# fre_oa.net
KiCad netlist of a schematic drawn in Altium Designer
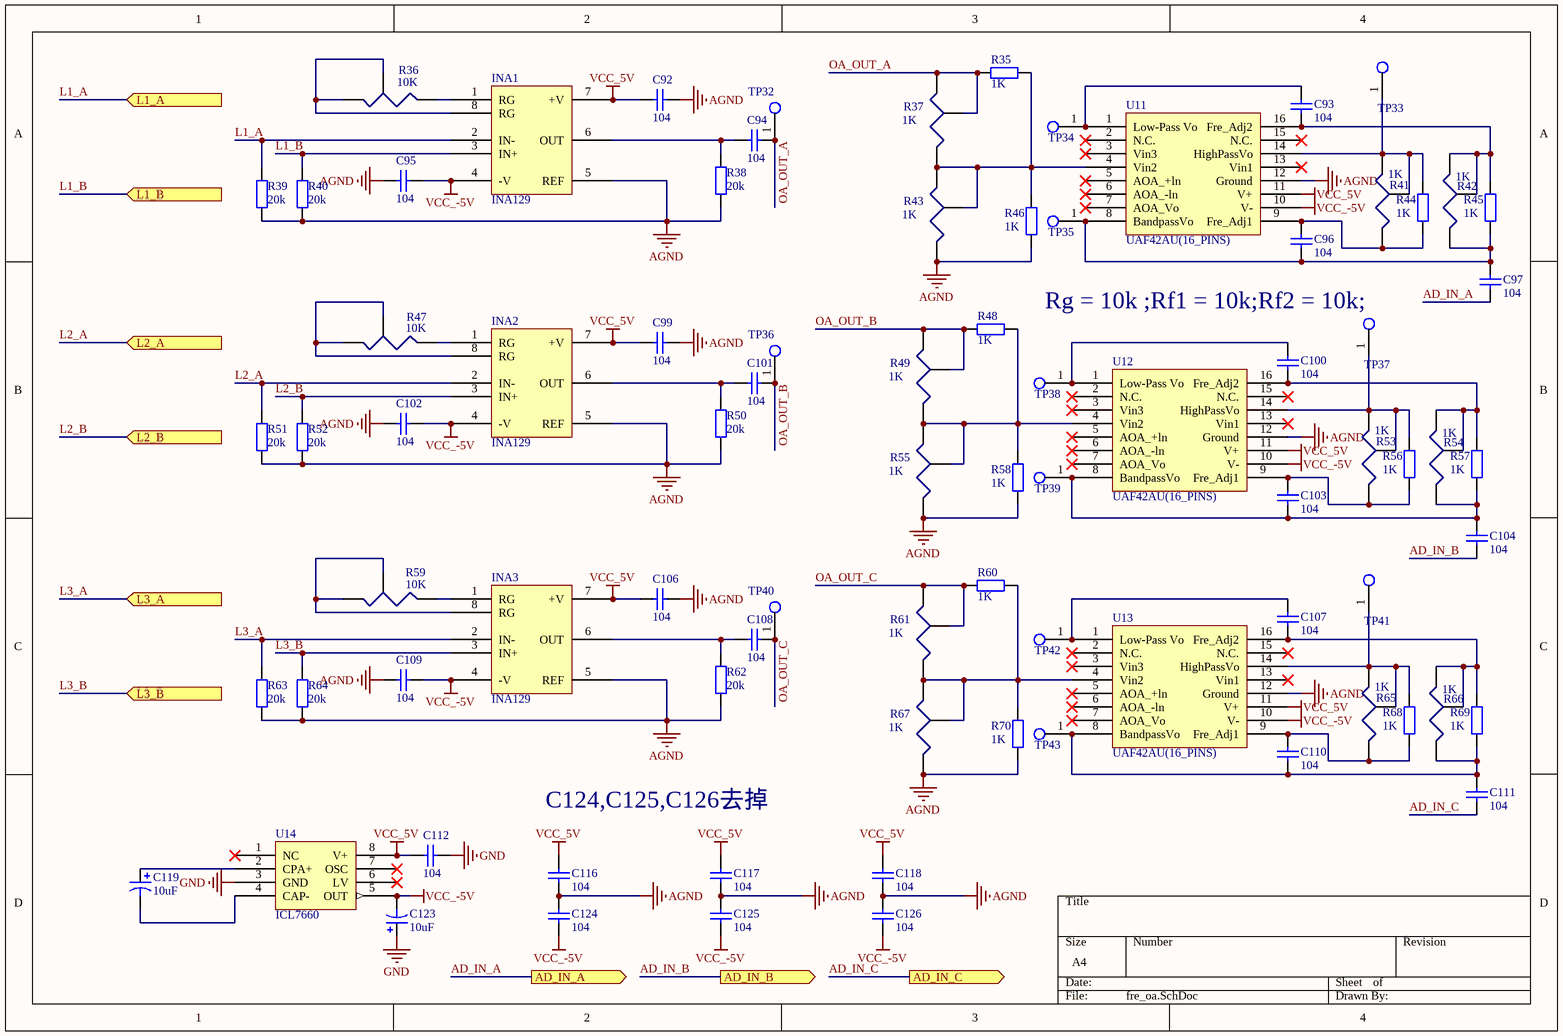
[diagram p0: fre_oa.SchDoc]

(export (version "E")
  (design (tool "Eeschema 10.0.6"))
  (components
    (comp (ref "C92")
      (value "104")
      (footprint "0603")
      (fields (field (name "Comment") "Cap"))
      (libsource (lib "自动化研究所集成库20170318") (part "Cap"))
    )
    (comp (ref "C93")
      (value "104")
      (footprint "0603")
      (fields (field (name "Comment") "Cap"))
      (libsource (lib "自动化研究所集成库20170318") (part "Cap"))
    )
    (comp (ref "C94")
      (value "104")
      (footprint "0603")
      (fields (field (name "Comment") "Cap"))
      (libsource (lib "自动化研究所集成库20170318") (part "Cap"))
    )
    (comp (ref "C95")
      (value "104")
      (footprint "0603")
      (fields (field (name "Comment") "Cap"))
      (libsource (lib "自动化研究所集成库20170318") (part "Cap"))
    )
    (comp (ref "C96")
      (value "104")
      (footprint "0603")
      (fields (field (name "Comment") "Cap"))
      (libsource (lib "自动化研究所集成库20170318") (part "Cap"))
    )
    (comp (ref "C97")
      (value "104")
      (footprint "0603")
      (fields (field (name "Comment") "Cap"))
      (libsource (lib "自动化研究所集成库20170318") (part "Cap"))
    )
    (comp (ref "C99")
      (value "104")
      (footprint "0603")
      (fields (field (name "Comment") "Cap"))
      (libsource (lib "自动化研究所集成库20170318") (part "Cap"))
    )
    (comp (ref "C100")
      (value "104")
      (footprint "0603")
      (fields (field (name "Comment") "Cap"))
      (libsource (lib "自动化研究所集成库20170318") (part "Cap"))
    )
    (comp (ref "C101")
      (value "104")
      (footprint "0603")
      (fields (field (name "Comment") "Cap"))
      (libsource (lib "自动化研究所集成库20170318") (part "Cap"))
    )
    (comp (ref "C102")
      (value "104")
      (footprint "0603")
      (fields (field (name "Comment") "Cap"))
      (libsource (lib "自动化研究所集成库20170318") (part "Cap"))
    )
    (comp (ref "C103")
      (value "104")
      (footprint "0603")
      (fields (field (name "Comment") "Cap"))
      (libsource (lib "自动化研究所集成库20170318") (part "Cap"))
    )
    (comp (ref "C104")
      (value "104")
      (footprint "0603")
      (fields (field (name "Comment") "Cap"))
      (libsource (lib "自动化研究所集成库20170318") (part "Cap"))
    )
    (comp (ref "C106")
      (value "104")
      (footprint "0603")
      (fields (field (name "Comment") "Cap"))
      (libsource (lib "自动化研究所集成库20170318") (part "Cap"))
    )
    (comp (ref "C107")
      (value "104")
      (footprint "0603")
      (fields (field (name "Comment") "Cap"))
      (libsource (lib "自动化研究所集成库20170318") (part "Cap"))
    )
    (comp (ref "C108")
      (value "104")
      (footprint "0603")
      (fields (field (name "Comment") "Cap"))
      (libsource (lib "自动化研究所集成库20170318") (part "Cap"))
    )
    (comp (ref "C109")
      (value "104")
      (footprint "0603")
      (fields (field (name "Comment") "Cap"))
      (libsource (lib "自动化研究所集成库20170318") (part "Cap"))
    )
    (comp (ref "C110")
      (value "104")
      (footprint "0603")
      (fields (field (name "Comment") "Cap"))
      (libsource (lib "自动化研究所集成库20170318") (part "Cap"))
    )
    (comp (ref "C111")
      (value "104")
      (footprint "0603")
      (fields (field (name "Comment") "Cap"))
      (libsource (lib "自动化研究所集成库20170318") (part "Cap"))
    )
    (comp (ref "C112")
      (value "104")
      (footprint "0603")
      (fields (field (name "Comment") "Cap"))
      (libsource (lib "自动化研究所集成库20170318") (part "Cap"))
    )
    (comp (ref "C116")
      (value "104")
      (footprint "0603")
      (fields (field (name "Comment") "Cap"))
      (libsource (lib "自动化研究所集成库20170318") (part "Cap"))
    )
    (comp (ref "C117")
      (value "104")
      (footprint "0603")
      (fields (field (name "Comment") "Cap"))
      (libsource (lib "自动化研究所集成库20170318") (part "Cap"))
    )
    (comp (ref "C118")
      (value "104")
      (footprint "0603")
      (fields (field (name "Comment") "Cap"))
      (libsource (lib "自动化研究所集成库20170318") (part "Cap"))
    )
    (comp (ref "C119")
      (value "10uF")
      (footprint "Cap 3528B")
      (fields (field (name "Comment") "Cap Poll"))
      (libsource (lib "自动化研究所集成库20170318") (part "Cap Poll"))
    )
    (comp (ref "C123")
      (value "10uF")
      (footprint "Cap 3528B")
      (fields (field (name "Comment") "Cap Poll"))
      (libsource (lib "自动化研究所集成库20170318") (part "Cap Poll"))
    )
    (comp (ref "C124")
      (value "104")
      (footprint "0603")
      (fields (field (name "Comment") "Cap"))
      (libsource (lib "自动化研究所集成库20170318") (part "Cap"))
    )
    (comp (ref "C125")
      (value "104")
      (footprint "0603")
      (fields (field (name "Comment") "Cap"))
      (libsource (lib "自动化研究所集成库20170318") (part "Cap"))
    )
    (comp (ref "C126")
      (value "104")
      (footprint "0603")
      (fields (field (name "Comment") "Cap"))
      (libsource (lib "自动化研究所集成库20170318") (part "Cap"))
    )
    (comp (ref "INA1") (value "INA129") (footprint "LM386") (libsource (lib "Sensor") (part "INA129")))
    (comp (ref "INA2") (value "INA129") (footprint "LM386") (libsource (lib "Sensor") (part "INA129")))
    (comp (ref "INA3") (value "INA129") (footprint "LM386") (libsource (lib "Sensor") (part "INA129")))
    (comp (ref "R35")
      (value "1K")
      (footprint "0603")
      (fields (field (name "Comment") "Res"))
      (libsource (lib "") (part "Res_1"))
    )
    (comp (ref "R36")
      (value "10K")
      (footprint "电位器WH06-2C")
      (fields (field (name "Comment") "电位器"))
      (libsource (lib "自动化研究所集成库20170318") (part "电位器"))
    )
    (comp (ref "R37")
      (value "1K")
      (footprint "电位器WH06-2C")
      (fields (field (name "Comment") "电位器"))
      (libsource (lib "自动化研究所集成库20170318") (part "电位器"))
    )
    (comp (ref "R38")
      (value "20k")
      (footprint "0603")
      (fields (field (name "Comment") "Res"))
      (libsource (lib "自动化研究所集成库20170318") (part "Res"))
    )
    (comp (ref "R39")
      (value "20k")
      (footprint "0603")
      (fields (field (name "Comment") "Res"))
      (libsource (lib "自动化研究所集成库20170318") (part "Res"))
    )
    (comp (ref "R40")
      (value "20k")
      (footprint "0603")
      (fields (field (name "Comment") "Res"))
      (libsource (lib "自动化研究所集成库20170318") (part "Res"))
    )
    (comp (ref "R41")
      (value "1K")
      (footprint "电位器WH06-2C")
      (fields (field (name "Comment") "电位器"))
      (libsource (lib "自动化研究所集成库20170318") (part "电位器"))
    )
    (comp (ref "R42")
      (value "1K")
      (footprint "电位器WH06-2C")
      (fields (field (name "Comment") "电位器"))
      (libsource (lib "自动化研究所集成库20170318") (part "电位器"))
    )
    (comp (ref "R43")
      (value "1K")
      (footprint "电位器WH06-2C")
      (fields (field (name "Comment") "电位器"))
      (libsource (lib "自动化研究所集成库20170318") (part "电位器"))
    )
    (comp (ref "R44")
      (value "1K")
      (footprint "0603")
      (fields (field (name "Comment") "Res"))
      (libsource (lib "自动化研究所集成库20170318") (part "Res"))
    )
    (comp (ref "R45")
      (value "1K")
      (footprint "0603")
      (fields (field (name "Comment") "Res"))
      (libsource (lib "自动化研究所集成库20170318") (part "Res"))
    )
    (comp (ref "R46")
      (value "1K")
      (footprint "0603")
      (fields (field (name "Comment") "Res"))
      (libsource (lib "自动化研究所集成库20170318") (part "Res"))
    )
    (comp (ref "R47")
      (value "10K")
      (footprint "电位器WH06-2C")
      (fields (field (name "Comment") "电位器"))
      (libsource (lib "自动化研究所集成库20170318") (part "电位器"))
    )
    (comp (ref "R48")
      (value "1K")
      (footprint "0603")
      (fields (field (name "Comment") "Res"))
      (libsource (lib "") (part "Res_1"))
    )
    (comp (ref "R49")
      (value "1K")
      (footprint "电位器WH06-2C")
      (fields (field (name "Comment") "电位器"))
      (libsource (lib "自动化研究所集成库20170318") (part "电位器"))
    )
    (comp (ref "R50")
      (value "20k")
      (footprint "0603")
      (fields (field (name "Comment") "Res"))
      (libsource (lib "自动化研究所集成库20170318") (part "Res"))
    )
    (comp (ref "R51")
      (value "20k")
      (footprint "0603")
      (fields (field (name "Comment") "Res"))
      (libsource (lib "自动化研究所集成库20170318") (part "Res"))
    )
    (comp (ref "R52")
      (value "20k")
      (footprint "0603")
      (fields (field (name "Comment") "Res"))
      (libsource (lib "自动化研究所集成库20170318") (part "Res"))
    )
    (comp (ref "R53")
      (value "1K")
      (footprint "电位器WH06-2C")
      (fields (field (name "Comment") "电位器"))
      (libsource (lib "自动化研究所集成库20170318") (part "电位器"))
    )
    (comp (ref "R54")
      (value "1K")
      (footprint "电位器WH06-2C")
      (fields (field (name "Comment") "电位器"))
      (libsource (lib "自动化研究所集成库20170318") (part "电位器"))
    )
    (comp (ref "R55")
      (value "1K")
      (footprint "电位器WH06-2C")
      (fields (field (name "Comment") "电位器"))
      (libsource (lib "自动化研究所集成库20170318") (part "电位器"))
    )
    (comp (ref "R56")
      (value "1K")
      (footprint "0603")
      (fields (field (name "Comment") "Res"))
      (libsource (lib "自动化研究所集成库20170318") (part "Res"))
    )
    (comp (ref "R57")
      (value "1K")
      (footprint "0603")
      (fields (field (name "Comment") "Res"))
      (libsource (lib "自动化研究所集成库20170318") (part "Res"))
    )
    (comp (ref "R58")
      (value "1K")
      (footprint "0603")
      (fields (field (name "Comment") "Res"))
      (libsource (lib "自动化研究所集成库20170318") (part "Res"))
    )
    (comp (ref "R59")
      (value "10K")
      (footprint "电位器WH06-2C")
      (fields (field (name "Comment") "电位器"))
      (libsource (lib "自动化研究所集成库20170318") (part "电位器"))
    )
    (comp (ref "R60")
      (value "1K")
      (footprint "0603")
      (fields (field (name "Comment") "Res"))
      (libsource (lib "") (part "Res_1"))
    )
    (comp (ref "R61")
      (value "1K")
      (footprint "电位器WH06-2C")
      (fields (field (name "Comment") "电位器"))
      (libsource (lib "自动化研究所集成库20170318") (part "电位器"))
    )
    (comp (ref "R62")
      (value "20k")
      (footprint "0603")
      (fields (field (name "Comment") "Res"))
      (libsource (lib "自动化研究所集成库20170318") (part "Res"))
    )
    (comp (ref "R63")
      (value "20k")
      (footprint "0603")
      (fields (field (name "Comment") "Res"))
      (libsource (lib "自动化研究所集成库20170318") (part "Res"))
    )
    (comp (ref "R64")
      (value "20k")
      (footprint "0603")
      (fields (field (name "Comment") "Res"))
      (libsource (lib "自动化研究所集成库20170318") (part "Res"))
    )
    (comp (ref "R65")
      (value "1K")
      (footprint "电位器WH06-2C")
      (fields (field (name "Comment") "电位器"))
      (libsource (lib "自动化研究所集成库20170318") (part "电位器"))
    )
    (comp (ref "R66")
      (value "1K")
      (footprint "电位器WH06-2C")
      (fields (field (name "Comment") "电位器"))
      (libsource (lib "自动化研究所集成库20170318") (part "电位器"))
    )
    (comp (ref "R67")
      (value "1K")
      (footprint "电位器WH06-2C")
      (fields (field (name "Comment") "电位器"))
      (libsource (lib "自动化研究所集成库20170318") (part "电位器"))
    )
    (comp (ref "R68")
      (value "1K")
      (footprint "0603")
      (fields (field (name "Comment") "Res"))
      (libsource (lib "自动化研究所集成库20170318") (part "Res"))
    )
    (comp (ref "R69")
      (value "1K")
      (footprint "0603")
      (fields (field (name "Comment") "Res"))
      (libsource (lib "自动化研究所集成库20170318") (part "Res"))
    )
    (comp (ref "R70")
      (value "1K")
      (footprint "0603")
      (fields (field (name "Comment") "Res"))
      (libsource (lib "自动化研究所集成库20170318") (part "Res"))
    )
    (comp (ref "TP32") (value "testPoint") (footprint "TP_H") (libsource (lib "Spartan") (part "TP")))
    (comp (ref "TP33") (value "testPoint") (footprint "TP_H") (libsource (lib "Spartan") (part "TP")))
    (comp (ref "TP34") (value "testPoint") (footprint "TP_H") (libsource (lib "Spartan") (part "TP")))
    (comp (ref "TP35") (value "testPoint") (footprint "TP_H") (libsource (lib "Spartan") (part "TP")))
    (comp (ref "TP36") (value "testPoint") (footprint "TP_H") (libsource (lib "Spartan") (part "TP")))
    (comp (ref "TP37") (value "testPoint") (footprint "TP_H") (libsource (lib "Spartan") (part "TP")))
    (comp (ref "TP38") (value "testPoint") (footprint "TP_H") (libsource (lib "Spartan") (part "TP")))
    (comp (ref "TP39") (value "testPoint") (footprint "TP_H") (libsource (lib "Spartan") (part "TP")))
    (comp (ref "TP40") (value "testPoint") (footprint "TP_H") (libsource (lib "Spartan") (part "TP")))
    (comp (ref "TP41") (value "testPoint") (footprint "TP_H") (libsource (lib "Spartan") (part "TP")))
    (comp (ref "TP42") (value "testPoint") (footprint "TP_H") (libsource (lib "Spartan") (part "TP")))
    (comp (ref "TP43") (value "testPoint") (footprint "TP_H") (libsource (lib "Spartan") (part "TP")))
    (comp (ref "U11")
      (value "UAF42AU(16_PINS)")
      (footprint "SOIC127P1030X265-16N")
      (libsource (lib "Dugu") (part "UAF42AU(16_PINS)"))
    )
    (comp (ref "U12")
      (value "UAF42AU(16_PINS)")
      (footprint "SOIC127P1030X265-16N")
      (libsource (lib "Dugu") (part "UAF42AU(16_PINS)"))
    )
    (comp (ref "U13")
      (value "UAF42AU(16_PINS)")
      (footprint "SOIC127P1030X265-16N")
      (libsource (lib "Dugu") (part "UAF42AU(16_PINS)"))
    )
    (comp (ref "U14")
      (value "ICL7660")
      (footprint "ICL7660 sop-8")
      (libsource (lib "自动化研究所集成库20170318") (part "ICL7660"))
    )
  )
  (nets
    (net (code "1") (name "/AD_IN_A") (class "Default")
      (node (ref "C97") (pin "2") (pinfunction "2_2") (pintype "passive"))
    )
    (net (code "2") (name "/AD_IN_B") (class "Default")
      (node (ref "C104") (pin "2") (pinfunction "2_2") (pintype "passive"))
    )
    (net (code "3") (name "/AD_IN_C") (class "Default")
      (node (ref "C111") (pin "2") (pinfunction "2_2") (pintype "passive"))
    )
    (net (code "4") (name "/L1_A") (class "Default")
      (node (ref "INA1") (pin "2") (pinfunction "IN-_2") (pintype "passive"))
      (node (ref "R39") (pin "2") (pinfunction "2_2") (pintype "passive"))
    )
    (net (code "5") (name "/L1_B") (class "Default")
      (node (ref "INA1") (pin "3") (pinfunction "IN+_3") (pintype "passive"))
      (node (ref "R40") (pin "2") (pinfunction "2_2") (pintype "passive"))
    )
    (net (code "6") (name "/L2_A") (class "Default")
      (node (ref "INA2") (pin "2") (pinfunction "IN-_2") (pintype "passive"))
      (node (ref "R51") (pin "2") (pinfunction "2_2") (pintype "passive"))
    )
    (net (code "7") (name "/L2_B") (class "Default")
      (node (ref "INA2") (pin "3") (pinfunction "IN+_3") (pintype "passive"))
      (node (ref "R52") (pin "2") (pinfunction "2_2") (pintype "passive"))
    )
    (net (code "8") (name "/L3_A") (class "Default")
      (node (ref "INA3") (pin "2") (pinfunction "IN-_2") (pintype "passive"))
      (node (ref "R63") (pin "2") (pinfunction "2_2") (pintype "passive"))
    )
    (net (code "9") (name "/L3_B") (class "Default")
      (node (ref "INA3") (pin "3") (pinfunction "IN+_3") (pintype "passive"))
      (node (ref "R64") (pin "2") (pinfunction "2_2") (pintype "passive"))
    )
    (net (code "10") (name "/OA_OUT_A") (class "Default")
      (node (ref "C94") (pin "2") (pinfunction "2_2") (pintype "passive"))
      (node (ref "R35") (pin "1") (pinfunction "1_1") (pintype "passive"))
      (node (ref "R37") (pin "2") (pintype "passive"))
      (node (ref "R37") (pin "3") (pintype "passive"))
      (node (ref "TP32") (pin "1") (pinfunction "1_1") (pintype "passive"))
    )
    (net (code "11") (name "/OA_OUT_B") (class "Default")
      (node (ref "C101") (pin "2") (pinfunction "2_2") (pintype "passive"))
      (node (ref "R48") (pin "1") (pinfunction "1_1") (pintype "passive"))
      (node (ref "R49") (pin "2") (pintype "passive"))
      (node (ref "R49") (pin "3") (pintype "passive"))
      (node (ref "TP36") (pin "1") (pinfunction "1_1") (pintype "passive"))
    )
    (net (code "12") (name "/OA_OUT_C") (class "Default")
      (node (ref "C108") (pin "2") (pinfunction "2_2") (pintype "passive"))
      (node (ref "R60") (pin "1") (pinfunction "1_1") (pintype "passive"))
      (node (ref "R61") (pin "2") (pintype "passive"))
      (node (ref "R61") (pin "3") (pintype "passive"))
      (node (ref "TP40") (pin "1") (pinfunction "1_1") (pintype "passive"))
    )
    (net (code "13") (name "AGND") (class "Default")
      (node (ref "C102") (pin "1") (pinfunction "1_1") (pintype "passive"))
      (node (ref "C106") (pin "2") (pinfunction "2_2") (pintype "passive"))
      (node (ref "C109") (pin "1") (pinfunction "1_1") (pintype "passive"))
      (node (ref "C116") (pin "1") (pinfunction "1_1") (pintype "passive"))
      (node (ref "C117") (pin "1") (pinfunction "1_1") (pintype "passive"))
      (node (ref "C118") (pin "1") (pinfunction "1_1") (pintype "passive"))
      (node (ref "C124") (pin "2") (pinfunction "2_2") (pintype "passive"))
      (node (ref "C125") (pin "2") (pinfunction "2_2") (pintype "passive"))
      (node (ref "C126") (pin "2") (pinfunction "2_2") (pintype "passive"))
      (node (ref "C92") (pin "2") (pinfunction "2_2") (pintype "passive"))
      (node (ref "C95") (pin "1") (pinfunction "1_1") (pintype "passive"))
      (node (ref "C99") (pin "2") (pinfunction "2_2") (pintype "passive"))
      (node (ref "INA1") (pin "5") (pinfunction "REF_5") (pintype "passive"))
      (node (ref "INA2") (pin "5") (pinfunction "REF_5") (pintype "passive"))
      (node (ref "INA3") (pin "5") (pinfunction "REF_5") (pintype "passive"))
      (node (ref "R38") (pin "1") (pinfunction "1_1") (pintype "passive"))
      (node (ref "R39") (pin "1") (pinfunction "1_1") (pintype "passive"))
      (node (ref "R40") (pin "1") (pinfunction "1_1") (pintype "passive"))
      (node (ref "R43") (pin "1") (pintype "passive"))
      (node (ref "R46") (pin "1") (pinfunction "1_1") (pintype "passive"))
      (node (ref "R50") (pin "1") (pinfunction "1_1") (pintype "passive"))
      (node (ref "R51") (pin "1") (pinfunction "1_1") (pintype "passive"))
      (node (ref "R52") (pin "1") (pinfunction "1_1") (pintype "passive"))
      (node (ref "R55") (pin "1") (pintype "passive"))
      (node (ref "R58") (pin "1") (pinfunction "1_1") (pintype "passive"))
      (node (ref "R62") (pin "1") (pinfunction "1_1") (pintype "passive"))
      (node (ref "R63") (pin "1") (pinfunction "1_1") (pintype "passive"))
      (node (ref "R64") (pin "1") (pinfunction "1_1") (pintype "passive"))
      (node (ref "R67") (pin "1") (pintype "passive"))
      (node (ref "R70") (pin "1") (pinfunction "1_1") (pintype "passive"))
      (node (ref "U11") (pin "12") (pinfunction "Ground_12") (pintype "passive"))
      (node (ref "U12") (pin "12") (pinfunction "Ground_12") (pintype "passive"))
      (node (ref "U13") (pin "12") (pinfunction "Ground_12") (pintype "passive"))
    )
    (net (code "14") (name "GND") (class "Default")
      (node (ref "C112") (pin "2") (pinfunction "2_2") (pintype "passive"))
      (node (ref "C123") (pin "1") (pinfunction "1_1") (pintype "passive"))
      (node (ref "U14") (pin "3") (pinfunction "GND_3") (pintype "power_in"))
    )
    (net (code "15") (name "Net-(INA1-OUT)") (class "Default")
      (node (ref "C94") (pin "1") (pinfunction "1_1") (pintype "passive"))
      (node (ref "INA1") (pin "6") (pinfunction "OUT_6") (pintype "passive"))
      (node (ref "R38") (pin "2") (pinfunction "2_2") (pintype "passive"))
    )
    (net (code "16") (name "Net-(INA1-RG-Pad1)") (class "Default")
      (node (ref "INA1") (pin "1") (pinfunction "RG_1") (pintype "passive"))
      (node (ref "R36") (pin "1") (pintype "passive"))
    )
    (net (code "17") (name "Net-(INA1-RG-Pad8)") (class "Default")
      (node (ref "INA1") (pin "8") (pinfunction "RG_8") (pintype "passive"))
      (node (ref "R36") (pin "2") (pintype "passive"))
      (node (ref "R36") (pin "3") (pintype "passive"))
    )
    (net (code "18") (name "Net-(INA2-OUT)") (class "Default")
      (node (ref "C101") (pin "1") (pinfunction "1_1") (pintype "passive"))
      (node (ref "INA2") (pin "6") (pinfunction "OUT_6") (pintype "passive"))
      (node (ref "R50") (pin "2") (pinfunction "2_2") (pintype "passive"))
    )
    (net (code "19") (name "Net-(INA2-RG-Pad1)") (class "Default")
      (node (ref "INA2") (pin "1") (pinfunction "RG_1") (pintype "passive"))
      (node (ref "R47") (pin "1") (pintype "passive"))
    )
    (net (code "20") (name "Net-(INA2-RG-Pad8)") (class "Default")
      (node (ref "INA2") (pin "8") (pinfunction "RG_8") (pintype "passive"))
      (node (ref "R47") (pin "2") (pintype "passive"))
      (node (ref "R47") (pin "3") (pintype "passive"))
    )
    (net (code "21") (name "Net-(INA3-OUT)") (class "Default")
      (node (ref "C108") (pin "1") (pinfunction "1_1") (pintype "passive"))
      (node (ref "INA3") (pin "6") (pinfunction "OUT_6") (pintype "passive"))
      (node (ref "R62") (pin "2") (pinfunction "2_2") (pintype "passive"))
    )
    (net (code "22") (name "Net-(INA3-RG-Pad1)") (class "Default")
      (node (ref "INA3") (pin "1") (pinfunction "RG_1") (pintype "passive"))
      (node (ref "R59") (pin "1") (pintype "passive"))
    )
    (net (code "23") (name "Net-(INA3-RG-Pad8)") (class "Default")
      (node (ref "INA3") (pin "8") (pinfunction "RG_8") (pintype "passive"))
      (node (ref "R59") (pin "2") (pintype "passive"))
      (node (ref "R59") (pin "3") (pintype "passive"))
    )
    (net (code "24") (name "Net-(U11-BandpassVo)") (class "Default")
      (node (ref "C96") (pin "2") (pinfunction "2_2") (pintype "passive"))
      (node (ref "C97") (pin "1") (pinfunction "1_1") (pintype "passive"))
      (node (ref "R42") (pin "1") (pintype "passive"))
      (node (ref "R45") (pin "1") (pinfunction "1_1") (pintype "passive"))
      (node (ref "TP35") (pin "1") (pinfunction "1_1") (pintype "passive"))
      (node (ref "U11") (pin "8") (pinfunction "BandpassVo_8") (pintype "power_in"))
    )
    (net (code "25") (name "Net-(U11-Fre_Adj1)") (class "Default")
      (node (ref "C96") (pin "1") (pinfunction "1_1") (pintype "passive"))
      (node (ref "R41") (pin "1") (pintype "passive"))
      (node (ref "R44") (pin "1") (pinfunction "1_1") (pintype "passive"))
      (node (ref "U11") (pin "9") (pinfunction "Fre_Adj1_9") (pintype "passive"))
    )
    (net (code "26") (name "Net-(U11-Fre_Adj2)") (class "Default")
      (node (ref "C93") (pin "2") (pinfunction "2_2") (pintype "passive"))
      (node (ref "R42") (pin "2") (pintype "passive"))
      (node (ref "R42") (pin "3") (pintype "passive"))
      (node (ref "R45") (pin "2") (pinfunction "2_2") (pintype "passive"))
      (node (ref "U11") (pin "16") (pinfunction "Fre_Adj2_16") (pintype "power_in"))
    )
    (net (code "27") (name "Net-(U11-HighPassVo)") (class "Default")
      (node (ref "R41") (pin "2") (pintype "passive"))
      (node (ref "R41") (pin "3") (pintype "passive"))
      (node (ref "R44") (pin "2") (pinfunction "2_2") (pintype "passive"))
      (node (ref "TP33") (pin "1") (pinfunction "1_1") (pintype "passive"))
      (node (ref "U11") (pin "14") (pinfunction "HighPassVo_14") (pintype "passive"))
    )
    (net (code "28") (name "Net-(U11-Low-Pass_Vo)") (class "Default")
      (node (ref "C93") (pin "1") (pinfunction "1_1") (pintype "passive"))
      (node (ref "TP34") (pin "1") (pinfunction "1_1") (pintype "passive"))
      (node (ref "U11") (pin "1") (pinfunction "Low-Pass_Vo_1") (pintype "passive"))
    )
    (net (code "29") (name "Net-(U11-Vin2)") (class "Default")
      (node (ref "R35") (pin "2") (pinfunction "2_2") (pintype "passive"))
      (node (ref "R37") (pin "1") (pintype "passive"))
      (node (ref "R43") (pin "2") (pintype "passive"))
      (node (ref "R43") (pin "3") (pintype "passive"))
      (node (ref "R46") (pin "2") (pinfunction "2_2") (pintype "passive"))
      (node (ref "U11") (pin "4") (pinfunction "Vin2_4") (pintype "passive"))
    )
    (net (code "30") (name "Net-(U12-BandpassVo)") (class "Default")
      (node (ref "C103") (pin "2") (pinfunction "2_2") (pintype "passive"))
      (node (ref "C104") (pin "1") (pinfunction "1_1") (pintype "passive"))
      (node (ref "R54") (pin "1") (pintype "passive"))
      (node (ref "R57") (pin "1") (pinfunction "1_1") (pintype "passive"))
      (node (ref "TP39") (pin "1") (pinfunction "1_1") (pintype "passive"))
      (node (ref "U12") (pin "8") (pinfunction "BandpassVo_8") (pintype "power_in"))
    )
    (net (code "31") (name "Net-(U12-Fre_Adj1)") (class "Default")
      (node (ref "C103") (pin "1") (pinfunction "1_1") (pintype "passive"))
      (node (ref "R53") (pin "1") (pintype "passive"))
      (node (ref "R56") (pin "1") (pinfunction "1_1") (pintype "passive"))
      (node (ref "U12") (pin "9") (pinfunction "Fre_Adj1_9") (pintype "passive"))
    )
    (net (code "32") (name "Net-(U12-Fre_Adj2)") (class "Default")
      (node (ref "C100") (pin "2") (pinfunction "2_2") (pintype "passive"))
      (node (ref "R54") (pin "2") (pintype "passive"))
      (node (ref "R54") (pin "3") (pintype "passive"))
      (node (ref "R57") (pin "2") (pinfunction "2_2") (pintype "passive"))
      (node (ref "U12") (pin "16") (pinfunction "Fre_Adj2_16") (pintype "power_in"))
    )
    (net (code "33") (name "Net-(U12-HighPassVo)") (class "Default")
      (node (ref "R53") (pin "2") (pintype "passive"))
      (node (ref "R53") (pin "3") (pintype "passive"))
      (node (ref "R56") (pin "2") (pinfunction "2_2") (pintype "passive"))
      (node (ref "TP37") (pin "1") (pinfunction "1_1") (pintype "passive"))
      (node (ref "U12") (pin "14") (pinfunction "HighPassVo_14") (pintype "passive"))
    )
    (net (code "34") (name "Net-(U12-Low-Pass_Vo)") (class "Default")
      (node (ref "C100") (pin "1") (pinfunction "1_1") (pintype "passive"))
      (node (ref "TP38") (pin "1") (pinfunction "1_1") (pintype "passive"))
      (node (ref "U12") (pin "1") (pinfunction "Low-Pass_Vo_1") (pintype "passive"))
    )
    (net (code "35") (name "Net-(U12-Vin2)") (class "Default")
      (node (ref "R48") (pin "2") (pinfunction "2_2") (pintype "passive"))
      (node (ref "R49") (pin "1") (pintype "passive"))
      (node (ref "R55") (pin "2") (pintype "passive"))
      (node (ref "R55") (pin "3") (pintype "passive"))
      (node (ref "R58") (pin "2") (pinfunction "2_2") (pintype "passive"))
      (node (ref "U12") (pin "4") (pinfunction "Vin2_4") (pintype "passive"))
    )
    (net (code "36") (name "Net-(U13-BandpassVo)") (class "Default")
      (node (ref "C110") (pin "2") (pinfunction "2_2") (pintype "passive"))
      (node (ref "C111") (pin "1") (pinfunction "1_1") (pintype "passive"))
      (node (ref "R66") (pin "1") (pintype "passive"))
      (node (ref "R69") (pin "1") (pinfunction "1_1") (pintype "passive"))
      (node (ref "TP43") (pin "1") (pinfunction "1_1") (pintype "passive"))
      (node (ref "U13") (pin "8") (pinfunction "BandpassVo_8") (pintype "power_in"))
    )
    (net (code "37") (name "Net-(U13-Fre_Adj1)") (class "Default")
      (node (ref "C110") (pin "1") (pinfunction "1_1") (pintype "passive"))
      (node (ref "R65") (pin "1") (pintype "passive"))
      (node (ref "R68") (pin "1") (pinfunction "1_1") (pintype "passive"))
      (node (ref "U13") (pin "9") (pinfunction "Fre_Adj1_9") (pintype "passive"))
    )
    (net (code "38") (name "Net-(U13-Fre_Adj2)") (class "Default")
      (node (ref "C107") (pin "2") (pinfunction "2_2") (pintype "passive"))
      (node (ref "R66") (pin "2") (pintype "passive"))
      (node (ref "R66") (pin "3") (pintype "passive"))
      (node (ref "R69") (pin "2") (pinfunction "2_2") (pintype "passive"))
      (node (ref "U13") (pin "16") (pinfunction "Fre_Adj2_16") (pintype "power_in"))
    )
    (net (code "39") (name "Net-(U13-HighPassVo)") (class "Default")
      (node (ref "R65") (pin "2") (pintype "passive"))
      (node (ref "R65") (pin "3") (pintype "passive"))
      (node (ref "R68") (pin "2") (pinfunction "2_2") (pintype "passive"))
      (node (ref "TP41") (pin "1") (pinfunction "1_1") (pintype "passive"))
      (node (ref "U13") (pin "14") (pinfunction "HighPassVo_14") (pintype "passive"))
    )
    (net (code "40") (name "Net-(U13-Low-Pass_Vo)") (class "Default")
      (node (ref "C107") (pin "1") (pinfunction "1_1") (pintype "passive"))
      (node (ref "TP42") (pin "1") (pinfunction "1_1") (pintype "passive"))
      (node (ref "U13") (pin "1") (pinfunction "Low-Pass_Vo_1") (pintype "passive"))
    )
    (net (code "41") (name "Net-(U13-Vin2)") (class "Default")
      (node (ref "R60") (pin "2") (pinfunction "2_2") (pintype "passive"))
      (node (ref "R61") (pin "1") (pintype "passive"))
      (node (ref "R67") (pin "2") (pintype "passive"))
      (node (ref "R67") (pin "3") (pintype "passive"))
      (node (ref "R70") (pin "2") (pinfunction "2_2") (pintype "passive"))
      (node (ref "U13") (pin "4") (pinfunction "Vin2_4") (pintype "passive"))
    )
    (net (code "42") (name "Net-(U14-CAP-)") (class "Default")
      (node (ref "C119") (pin "2") (pinfunction "2_2") (pintype "passive"))
      (node (ref "U14") (pin "4") (pinfunction "CAP-_4") (pintype "passive"))
    )
    (net (code "43") (name "Net-(U14-CPA+)") (class "Default")
      (node (ref "C119") (pin "1") (pinfunction "1_1") (pintype "passive"))
      (node (ref "U14") (pin "2") (pinfunction "CPA+_2") (pintype "passive"))
    )
    (net (code "44") (name "VCC_-5V") (class "Default")
      (node (ref "C102") (pin "2") (pinfunction "2_2") (pintype "passive"))
      (node (ref "C109") (pin "2") (pinfunction "2_2") (pintype "passive"))
      (node (ref "C123") (pin "2") (pinfunction "2_2") (pintype "passive"))
      (node (ref "C124") (pin "1") (pinfunction "1_1") (pintype "passive"))
      (node (ref "C125") (pin "1") (pinfunction "1_1") (pintype "passive"))
      (node (ref "C126") (pin "1") (pinfunction "1_1") (pintype "passive"))
      (node (ref "C95") (pin "2") (pinfunction "2_2") (pintype "passive"))
      (node (ref "INA1") (pin "4") (pinfunction "-V_4") (pintype "passive"))
      (node (ref "INA2") (pin "4") (pinfunction "-V_4") (pintype "passive"))
      (node (ref "INA3") (pin "4") (pinfunction "-V_4") (pintype "passive"))
      (node (ref "U11") (pin "10") (pinfunction "V-_10") (pintype "passive"))
      (node (ref "U12") (pin "10") (pinfunction "V-_10") (pintype "passive"))
      (node (ref "U13") (pin "10") (pinfunction "V-_10") (pintype "passive"))
      (node (ref "U14") (pin "5") (pinfunction "OUT_5") (pintype "output"))
    )
    (net (code "45") (name "VCC_5V") (class "Default")
      (node (ref "C106") (pin "1") (pinfunction "1_1") (pintype "passive"))
      (node (ref "C112") (pin "1") (pinfunction "1_1") (pintype "passive"))
      (node (ref "C116") (pin "2") (pinfunction "2_2") (pintype "passive"))
      (node (ref "C117") (pin "2") (pinfunction "2_2") (pintype "passive"))
      (node (ref "C118") (pin "2") (pinfunction "2_2") (pintype "passive"))
      (node (ref "C92") (pin "1") (pinfunction "1_1") (pintype "passive"))
      (node (ref "C99") (pin "1") (pinfunction "1_1") (pintype "passive"))
      (node (ref "INA1") (pin "7") (pinfunction "+V_7") (pintype "passive"))
      (node (ref "INA2") (pin "7") (pinfunction "+V_7") (pintype "passive"))
      (node (ref "INA3") (pin "7") (pinfunction "+V_7") (pintype "passive"))
      (node (ref "U11") (pin "11") (pinfunction "V+_11") (pintype "passive"))
      (node (ref "U12") (pin "11") (pinfunction "V+_11") (pintype "passive"))
      (node (ref "U13") (pin "11") (pinfunction "V+_11") (pintype "passive"))
      (node (ref "U14") (pin "8") (pinfunction "V+_8") (pintype "power_in"))
    )
    (net (code "46") (name "unconnected-(U11-AOA_+ln-Pad5)") (class "Default")
      (node (ref "U11") (pin "5") (pinfunction "AOA_+ln_5") (pintype "passive+no_connect"))
    )
    (net (code "47") (name "unconnected-(U11-AOA_-ln-Pad6)") (class "Default")
      (node (ref "U11") (pin "6") (pinfunction "AOA_-ln_6") (pintype "passive+no_connect"))
    )
    (net (code "48") (name "unconnected-(U11-AOA_Vo-Pad7)") (class "Default")
      (node (ref "U11") (pin "7") (pinfunction "AOA_Vo_7") (pintype "passive+no_connect"))
    )
    (net (code "49") (name "unconnected-(U11-N.C.-Pad2)") (class "Default")
      (node (ref "U11") (pin "2") (pinfunction "N.C._2") (pintype "passive+no_connect"))
    )
    (net (code "50") (name "unconnected-(U11-N.C.-Pad15)") (class "Default")
      (node (ref "U11") (pin "15") (pinfunction "N.C._15") (pintype "passive+no_connect"))
    )
    (net (code "51") (name "unconnected-(U11-Vin1-Pad13)") (class "Default")
      (node (ref "U11") (pin "13") (pinfunction "Vin1_13") (pintype "passive+no_connect"))
    )
    (net (code "52") (name "unconnected-(U11-Vin3-Pad3)") (class "Default")
      (node (ref "U11") (pin "3") (pinfunction "Vin3_3") (pintype "passive+no_connect"))
    )
    (net (code "53") (name "unconnected-(U12-AOA_+ln-Pad5)") (class "Default")
      (node (ref "U12") (pin "5") (pinfunction "AOA_+ln_5") (pintype "passive+no_connect"))
    )
    (net (code "54") (name "unconnected-(U12-AOA_-ln-Pad6)") (class "Default")
      (node (ref "U12") (pin "6") (pinfunction "AOA_-ln_6") (pintype "passive+no_connect"))
    )
    (net (code "55") (name "unconnected-(U12-AOA_Vo-Pad7)") (class "Default")
      (node (ref "U12") (pin "7") (pinfunction "AOA_Vo_7") (pintype "passive+no_connect"))
    )
    (net (code "56") (name "unconnected-(U12-N.C.-Pad2)") (class "Default")
      (node (ref "U12") (pin "2") (pinfunction "N.C._2") (pintype "passive+no_connect"))
    )
    (net (code "57") (name "unconnected-(U12-N.C.-Pad15)") (class "Default")
      (node (ref "U12") (pin "15") (pinfunction "N.C._15") (pintype "passive+no_connect"))
    )
    (net (code "58") (name "unconnected-(U12-Vin1-Pad13)") (class "Default")
      (node (ref "U12") (pin "13") (pinfunction "Vin1_13") (pintype "passive+no_connect"))
    )
    (net (code "59") (name "unconnected-(U12-Vin3-Pad3)") (class "Default")
      (node (ref "U12") (pin "3") (pinfunction "Vin3_3") (pintype "passive+no_connect"))
    )
    (net (code "60") (name "unconnected-(U13-AOA_+ln-Pad5)") (class "Default")
      (node (ref "U13") (pin "5") (pinfunction "AOA_+ln_5") (pintype "passive+no_connect"))
    )
    (net (code "61") (name "unconnected-(U13-AOA_-ln-Pad6)") (class "Default")
      (node (ref "U13") (pin "6") (pinfunction "AOA_-ln_6") (pintype "passive+no_connect"))
    )
    (net (code "62") (name "unconnected-(U13-AOA_Vo-Pad7)") (class "Default")
      (node (ref "U13") (pin "7") (pinfunction "AOA_Vo_7") (pintype "passive+no_connect"))
    )
    (net (code "63") (name "unconnected-(U13-N.C.-Pad2)") (class "Default")
      (node (ref "U13") (pin "2") (pinfunction "N.C._2") (pintype "passive+no_connect"))
    )
    (net (code "64") (name "unconnected-(U13-N.C.-Pad15)") (class "Default")
      (node (ref "U13") (pin "15") (pinfunction "N.C._15") (pintype "passive+no_connect"))
    )
    (net (code "65") (name "unconnected-(U13-Vin1-Pad13)") (class "Default")
      (node (ref "U13") (pin "13") (pinfunction "Vin1_13") (pintype "passive+no_connect"))
    )
    (net (code "66") (name "unconnected-(U13-Vin3-Pad3)") (class "Default")
      (node (ref "U13") (pin "3") (pinfunction "Vin3_3") (pintype "passive+no_connect"))
    )
    (net (code "67") (name "unconnected-(U14-LV-Pad6)") (class "Default")
      (node (ref "U14") (pin "6") (pinfunction "LV_6") (pintype "passive+no_connect"))
    )
    (net (code "68") (name "unconnected-(U14-NC-Pad1)") (class "Default")
      (node (ref "U14") (pin "1") (pinfunction "NC_1") (pintype "passive+no_connect"))
    )
    (net (code "69") (name "unconnected-(U14-OSC-Pad7)") (class "Default")
      (node (ref "U14") (pin "7") (pinfunction "OSC_7") (pintype "passive+no_connect"))
    )
  )
)
